# 20241105.net
KiCad netlist of a schematic drawn in Altium Designer
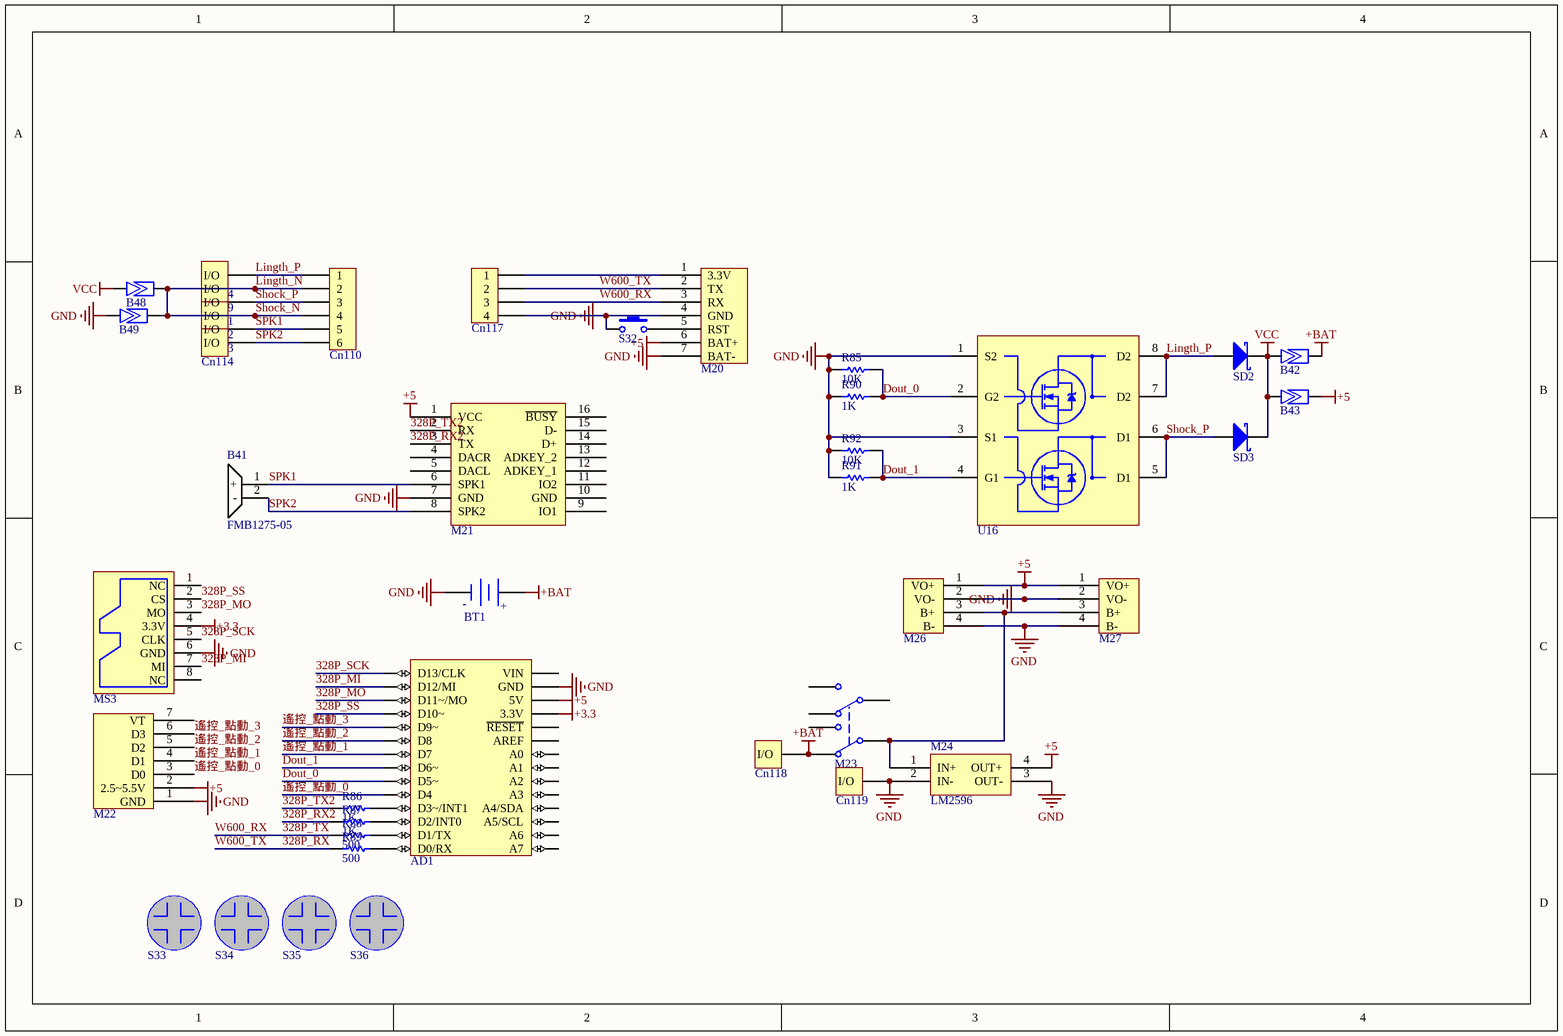
[diagram p0: 松菸_幻影光靈_屍禁_提燈_20241105.SchDoc]

(export (version "E")
  (design (tool "Eeschema 10.0.6"))
  (components
    (comp (ref "AD1")
      (value "Arduino NANO")
      (footprint "Arduino NANO")
      (description "單晶片")
      (libsource (lib "MyLibray") (part "Arduino NANO"))
    )
    (comp (ref "B41")
      (value "FMB1275-05")
      (footprint "Buzzer_12085")
      (description "無源蜂鳴器")
      (libsource (lib "MyLibray") (part "Buzzer"))
    )
    (comp (ref "B42")
      (value "短路")
      (footprint "BYPASS-0805")
      (description "短路焊點(如標註短路則需額外補錫使其短路)")
      (libsource (lib "MyLibray") (part "Bypass"))
    )
    (comp (ref "B43")
      (value "短路")
      (footprint "BYPASS-0805")
      (description "短路焊點(如標註短路則需額外補錫使其短路)")
      (libsource (lib "MyLibray") (part "Bypass"))
    )
    (comp (ref "B48")
      (value "短路")
      (footprint "BYPASS-0805")
      (description "短路焊點(如標註短路則需額外補錫使其短路)")
      (libsource (lib "MyLibray") (part "Bypass"))
    )
    (comp (ref "B49")
      (value "短路")
      (footprint "BYPASS-0805")
      (description "短路焊點(如標註短路則需額外補錫使其短路)")
      (libsource (lib "MyLibray") (part "Bypass"))
    )
    (comp (ref "BT1")
      (value "18650")
      (footprint "Battery_18650")
      (description "電池")
      (libsource (lib "MyLibray") (part "Battery"))
    )
    (comp (ref "Cn104")
      (value "Contact")
      (footprint "Conntact_Stamp hole_0.6\"")
      (description "接線端子、接點、郵票孔(非焊接元件)")
      (libsource (lib "MyLibray") (part "Conntact"))
    )
    (comp (ref "Cn109")
      (value "Contact")
      (footprint "Conntact_Stamp hole_0.6\"")
      (description "接線端子、接點、郵票孔(非焊接元件)")
      (libsource (lib "") (part "Conntact_1"))
    )
    (comp (ref "Cn110")
      (value "KF2510-6")
      (footprint "Connector_KF2510-6A")
      (description "連接器")
      (libsource (lib "MyLibray") (part "Conntact(6P)"))
    )
    (comp (ref "Cn111")
      (value "Contact")
      (footprint "Conntact_Stamp hole_0.6\"")
      (description "接線端子、接點、郵票孔(非焊接元件)")
      (libsource (lib "MyLibray") (part "Conntact"))
    )
    (comp (ref "Cn112")
      (value "Contact")
      (footprint "Conntact_Stamp hole_0.6\"")
      (description "接線端子、接點、郵票孔(非焊接元件)")
      (libsource (lib "MyLibray") (part "Conntact"))
    )
    (comp (ref "Cn113")
      (value "Contact")
      (footprint "Conntact_Stamp hole_0.6\"")
      (description "接線端子、接點、郵票孔(非焊接元件)")
      (libsource (lib "MyLibray") (part "Conntact"))
    )
    (comp (ref "Cn114")
      (value "Contact")
      (footprint "Conntact_Stamp hole_0.6\"")
      (description "接線端子、接點、郵票孔(非焊接元件)")
      (libsource (lib "MyLibray") (part "Conntact"))
    )
    (comp (ref "Cn117")
      (value "KF2510-4")
      (footprint "Connector_KF2510-4A")
      (description "連接器")
      (libsource (lib "MyLibray") (part "Conntact(4P)"))
    )
    (comp (ref "Cn118")
      (value "Contact")
      (footprint "Conntact_Stamp hole_0.6\"")
      (description "接線端子、接點、郵票孔(非焊接元件)")
      (libsource (lib "MyLibray") (part "Conntact"))
    )
    (comp (ref "Cn119")
      (value "Contact")
      (footprint "Conntact_Stamp hole_0.6\"")
      (description "接線端子、接點、郵票孔(非焊接元件)")
      (libsource (lib "MyLibray") (part "Conntact"))
    )
    (comp (ref "M20")
      (value "HH_W600_V2.0")
      (footprint "HH_W600_V2.0")
      (libsource (lib "MyLibray") (part "HH_W600_V2.0"))
    )
    (comp (ref "M21")
      (value "mp3-tf-16p")
      (footprint "BY8001-16P")
      (description "TTL通訊SD卡撥放mp3模組")
      (libsource (lib "MyLibray") (part "Mini MP3 Player"))
    )
    (comp (ref "M22")
      (value "XR390")
      (footprint "XR390 Module")
      (description "遙控器模組")
      (libsource (lib "MyLibray") (part "XR390"))
    )
    (comp (ref "M23")
      (value "MST22D18G2")
      (footprint "Switch_MST22D18G2")
      (description "開關_滑動_2通道")
      (libsource (lib "MyLibray") (part "Switch_Slide_2"))
    )
    (comp (ref "M24")
      (value "LM2596")
      (footprint "LM2596 Module")
      (description "DC to DC 降壓模組")
      (libsource (lib "MyLibray") (part "LM2596_Moduld"))
    )
    (comp (ref "M26")
      (value "4056+LN2220PAR_Module")
      (footprint "4056H+DW01A_Module")
      (description "鋰電池充電升壓模組")
      (libsource (lib "MyLibray") (part "4056+LN2220PAR_Module"))
    )
    (comp (ref "M27")
      (value "4056+LN2220PAR_Module")
      (footprint "4056H+DW01A_Module")
      (description "鋰電池充電升壓模組")
      (libsource (lib "") (part "4056+LN2220PAR_Module_1"))
    )
    (comp (ref "MS3")
      (value "Interface_MicroSD card slot")
      (footprint "Interface_MicroSD card slot")
      (description "Micro SD 卡座")
      (libsource (lib "MyLibray") (part "Interface_MicroSD card slot"))
    )
    (comp (ref "R85")
      (value "10K")
      (footprint "Res-1206")
      (description "電阻")
      (libsource (lib "MyLibray") (part "Res"))
    )
    (comp (ref "R86")
      (value "1K")
      (footprint "Res-1206")
      (description "電阻")
      (libsource (lib "MyLibray") (part "Res"))
    )
    (comp (ref "R87")
      (value "1K")
      (footprint "Res-1206")
      (description "電阻")
      (libsource (lib "MyLibray") (part "Res"))
    )
    (comp (ref "R88")
      (value "500")
      (footprint "Res-1206")
      (description "電阻")
      (libsource (lib "MyLibray") (part "Res"))
    )
    (comp (ref "R89")
      (value "500")
      (footprint "Res-1206")
      (description "電阻")
      (libsource (lib "MyLibray") (part "Res"))
    )
    (comp (ref "R90")
      (value "1K")
      (footprint "Res-1206")
      (description "電阻")
      (libsource (lib "MyLibray") (part "Res"))
    )
    (comp (ref "R91")
      (value "1K")
      (footprint "Res-1206")
      (description "電阻")
      (libsource (lib "MyLibray") (part "Res"))
    )
    (comp (ref "R92")
      (value "10K")
      (footprint "Res-1206")
      (description "電阻")
      (libsource (lib "MyLibray") (part "Res"))
    )
    (comp (ref "S32")
      (value "Switch")
      (footprint "Switch SMD-3.6*6*2.5")
      (description "開關_按鍵")
      (libsource (lib "MyLibray") (part "Switch"))
    )
    (comp (ref "S33")
      (value "M3")
      (footprint "Screw M3")
      (description "螺絲(非焊接元件)")
      (libsource (lib "MyLibray") (part "Screw"))
    )
    (comp (ref "S34")
      (value "M3")
      (footprint "Screw M3")
      (description "螺絲(非焊接元件)")
      (libsource (lib "MyLibray") (part "Screw"))
    )
    (comp (ref "S35")
      (value "M3")
      (footprint "Screw M3")
      (description "螺絲(非焊接元件)")
      (libsource (lib "MyLibray") (part "Screw"))
    )
    (comp (ref "S36")
      (value "M3")
      (footprint "Screw M3")
      (description "螺絲(非焊接元件)")
      (libsource (lib "MyLibray") (part "Screw"))
    )
    (comp (ref "SD2")
      (value "SS56")
      (footprint "Diode_SMA")
      (description "二極體_蕭特基")
      (libsource (lib "MyLibray") (part "Diode_Schottky"))
    )
    (comp (ref "SD3")
      (value "SS56")
      (footprint "Diode_SMA")
      (description "二極體_蕭特基")
      (libsource (lib "MyLibray") (part "Diode_Schottky"))
    )
    (comp (ref "U16")
      (value "AO4800")
      (footprint "SOP-8")
      (description "MOS,雙NMOS")
      (libsource (lib "MyLibray") (part "MOS_Dual N_AO4800"))
    )
  )
  (nets
    (net (code "1") (name "+3.3") (class "Default")
      (node (ref "AD1") (pin "5") (pinfunction "3.3V_5") (pintype "passive"))
      (node (ref "MS3") (pin "4") (pinfunction "3.3V_4") (pintype "power_in"))
    )
    (net (code "2") (name "+5") (class "Default")
      (node (ref "AD1") (pin "3") (pinfunction "5V_3") (pintype "passive"))
      (node (ref "B43") (pin "1") (pinfunction "1_1") (pintype "passive"))
      (node (ref "M20") (pin "6") (pinfunction "BAT+_6") (pintype "passive"))
      (node (ref "M21") (pin "1") (pinfunction "VCC_1") (pintype "passive"))
      (node (ref "M22") (pin "2") (pinfunction "2.5~5.5V_2") (pintype "passive"))
      (node (ref "M24") (pin "4") (pinfunction "OUT+_4") (pintype "passive"))
      (node (ref "M26") (pin "1") (pinfunction "VO+_1") (pintype "passive"))
      (node (ref "M27") (pin "1") (pinfunction "VO+_1") (pintype "passive"))
    )
    (net (code "3") (name "+BAT") (class "Default")
      (node (ref "B42") (pin "1") (pinfunction "1_1") (pintype "passive"))
      (node (ref "BT1") (pin "1") (pinfunction "+_1") (pintype "power_in"))
      (node (ref "Cn118") (pin "1") (pinfunction "I/O_1") (pintype "passive"))
      (node (ref "M23") (pin "2") (pinfunction "2_2") (pintype "passive"))
    )
    (net (code "4") (name "/328P_MI") (class "Default")
      (node (ref "AD1") (pin "19") (pinfunction "D12/MI_19") (pintype "bidirectional"))
      (node (ref "MS3") (pin "7") (pinfunction "MI_7") (pintype "passive"))
    )
    (net (code "5") (name "/328P_MO") (class "Default")
      (node (ref "AD1") (pin "18") (pinfunction "D11~/MO_18") (pintype "bidirectional"))
      (node (ref "MS3") (pin "3") (pinfunction "MO_3") (pintype "passive"))
    )
    (net (code "6") (name "/328P_RX") (class "Default")
      (node (ref "Cn117") (pin "2") (pinfunction "2_2") (pintype "passive"))
      (node (ref "M20") (pin "2") (pinfunction "TX_2") (pintype "passive"))
      (node (ref "R89") (pin "1") (pinfunction "1_1") (pintype "passive"))
    )
    (net (code "7") (name "/328P_RX2") (class "Default")
      (node (ref "M21") (pin "3") (pinfunction "TX_3") (pintype "passive"))
      (node (ref "R87") (pin "1") (pinfunction "1_1") (pintype "passive"))
    )
    (net (code "8") (name "/328P_SCK") (class "Default")
      (node (ref "AD1") (pin "20") (pinfunction "D13/CLK_20") (pintype "bidirectional"))
      (node (ref "MS3") (pin "5") (pinfunction "CLK_5") (pintype "passive"))
    )
    (net (code "9") (name "/328P_SS") (class "Default")
      (node (ref "AD1") (pin "17") (pinfunction "D10~_17") (pintype "bidirectional"))
      (node (ref "MS3") (pin "2") (pinfunction "CS_2") (pintype "passive"))
    )
    (net (code "10") (name "/328P_TX") (class "Default")
      (node (ref "Cn117") (pin "3") (pinfunction "3_3") (pintype "passive"))
      (node (ref "M20") (pin "3") (pinfunction "RX_3") (pintype "passive"))
      (node (ref "R88") (pin "1") (pinfunction "1_1") (pintype "passive"))
    )
    (net (code "11") (name "/328P_TX2") (class "Default")
      (node (ref "M21") (pin "2") (pinfunction "RX_2") (pintype "passive"))
      (node (ref "R86") (pin "1") (pinfunction "1_1") (pintype "passive"))
    )
    (net (code "12") (name "/Dout_0") (class "Default")
      (node (ref "AD1") (pin "12") (pinfunction "D5~_12") (pintype "bidirectional"))
      (node (ref "R85") (pin "2") (pinfunction "2_2") (pintype "passive"))
      (node (ref "R90") (pin "2") (pinfunction "2_2") (pintype "passive"))
      (node (ref "U16") (pin "2") (pinfunction "G2_2") (pintype "passive"))
    )
    (net (code "13") (name "/Dout_1") (class "Default")
      (node (ref "AD1") (pin "13") (pinfunction "D6~_13") (pintype "bidirectional"))
      (node (ref "R91") (pin "2") (pinfunction "2_2") (pintype "passive"))
      (node (ref "R92") (pin "2") (pinfunction "2_2") (pintype "passive"))
      (node (ref "U16") (pin "4") (pinfunction "G1_4") (pintype "passive"))
    )
    (net (code "14") (name "/Lingth_N") (class "Default")
      (node (ref "B48") (pin "1") (pinfunction "1_1") (pintype "passive"))
      (node (ref "B49") (pin "1") (pinfunction "1_1") (pintype "passive"))
      (node (ref "Cn109") (pin "1") (pinfunction "I/O_1") (pintype "passive"))
      (node (ref "Cn110") (pin "2") (pinfunction "2_2") (pintype "passive"))
      (node (ref "Cn110") (pin "4") (pinfunction "4_4") (pintype "passive"))
      (node (ref "Cn112") (pin "1") (pinfunction "I/O_1") (pintype "passive"))
    )
    (net (code "15") (name "/Lingth_P") (class "Default")
      (node (ref "Cn104") (pin "1") (pinfunction "I/O_1") (pintype "passive"))
      (node (ref "Cn110") (pin "1") (pinfunction "1_1") (pintype "passive"))
      (node (ref "SD2") (pin "2") (pinfunction "A_2") (pintype "passive"))
      (node (ref "U16") (pin "7") (pinfunction "D2_7") (pintype "passive"))
      (node (ref "U16") (pin "8") (pinfunction "D2_8") (pintype "passive"))
    )
    (net (code "16") (name "/SPK1") (class "Default")
      (node (ref "B41") (pin "1") (pinfunction "+_1") (pintype "passive"))
      (node (ref "Cn110") (pin "5") (pinfunction "5_5") (pintype "passive"))
      (node (ref "Cn113") (pin "1") (pinfunction "I/O_1") (pintype "passive"))
      (node (ref "M21") (pin "6") (pinfunction "SPK1_6") (pintype "passive"))
    )
    (net (code "17") (name "/SPK2") (class "Default")
      (node (ref "B41") (pin "2") (pinfunction "-_2") (pintype "passive"))
      (node (ref "Cn110") (pin "6") (pinfunction "6_6") (pintype "passive"))
      (node (ref "Cn114") (pin "1") (pinfunction "I/O_1") (pintype "passive"))
      (node (ref "M21") (pin "8") (pinfunction "SPK2_8") (pintype "passive"))
    )
    (net (code "18") (name "/Shock_P") (class "Default")
      (node (ref "Cn110") (pin "3") (pinfunction "3_3") (pintype "passive"))
      (node (ref "Cn111") (pin "1") (pinfunction "I/O_1") (pintype "passive"))
      (node (ref "SD3") (pin "2") (pinfunction "A_2") (pintype "passive"))
      (node (ref "U16") (pin "5") (pinfunction "D1_5") (pintype "passive"))
      (node (ref "U16") (pin "6") (pinfunction "D1_6") (pintype "passive"))
    )
    (net (code "19") (name "/遙控_點動_0") (class "Default")
      (node (ref "AD1") (pin "11") (pinfunction "D4_11") (pintype "bidirectional"))
      (node (ref "M22") (pin "3") (pinfunction "D0_3") (pintype "passive"))
    )
    (net (code "20") (name "/遙控_點動_1") (class "Default")
      (node (ref "AD1") (pin "14") (pinfunction "D7_14") (pintype "bidirectional"))
      (node (ref "M22") (pin "4") (pinfunction "D1_4") (pintype "passive"))
    )
    (net (code "21") (name "/遙控_點動_2") (class "Default")
      (node (ref "AD1") (pin "15") (pinfunction "D8_15") (pintype "bidirectional"))
      (node (ref "M22") (pin "5") (pinfunction "D2_5") (pintype "passive"))
    )
    (net (code "22") (name "/遙控_點動_3") (class "Default")
      (node (ref "AD1") (pin "16") (pinfunction "D9~_16") (pintype "bidirectional"))
      (node (ref "M22") (pin "6") (pinfunction "D3_6") (pintype "passive"))
    )
    (net (code "23") (name "GND") (class "Default")
      (node (ref "AD1") (pin "2") (pinfunction "GND_2") (pintype "passive"))
      (node (ref "B49") (pin "2") (pinfunction "2_2") (pintype "passive"))
      (node (ref "BT1") (pin "2") (pinfunction "-_2") (pintype "power_in"))
      (node (ref "Cn117") (pin "4") (pinfunction "4_4") (pintype "passive"))
      (node (ref "Cn119") (pin "1") (pinfunction "I/O_1") (pintype "passive"))
      (node (ref "M20") (pin "4") (pinfunction "GND_4") (pintype "passive"))
      (node (ref "M20") (pin "7") (pinfunction "BAT-_7") (pintype "passive"))
      (node (ref "M21") (pin "7") (pinfunction "GND_7") (pintype "passive"))
      (node (ref "M22") (pin "1") (pinfunction "GND_1") (pintype "passive"))
      (node (ref "M24") (pin "2") (pinfunction "IN-_2") (pintype "passive"))
      (node (ref "M24") (pin "3") (pinfunction "OUT-_3") (pintype "passive"))
      (node (ref "M26") (pin "2") (pinfunction "VO-_2") (pintype "passive"))
      (node (ref "M26") (pin "4") (pinfunction "B-_4") (pintype "passive"))
      (node (ref "M27") (pin "2") (pinfunction "VO-_2") (pintype "passive"))
      (node (ref "M27") (pin "4") (pinfunction "B-_4") (pintype "passive"))
      (node (ref "MS3") (pin "6") (pinfunction "GND_6") (pintype "power_in"))
      (node (ref "R85") (pin "1") (pinfunction "1_1") (pintype "passive"))
      (node (ref "R90") (pin "1") (pinfunction "1_1") (pintype "passive"))
      (node (ref "R91") (pin "1") (pinfunction "1_1") (pintype "passive"))
      (node (ref "R92") (pin "1") (pinfunction "1_1") (pintype "passive"))
      (node (ref "S32") (pin "1") (pinfunction "1_1") (pintype "passive"))
      (node (ref "U16") (pin "1") (pinfunction "S2_1") (pintype "passive"))
      (node (ref "U16") (pin "3") (pinfunction "S1_3") (pintype "passive"))
    )
    (net (code "24") (name "Net-(AD1-D0{slash}RX)") (class "Default")
      (node (ref "AD1") (pin "7") (pinfunction "D0/RX_7") (pintype "bidirectional"))
      (node (ref "R89") (pin "2") (pinfunction "2_2") (pintype "passive"))
    )
    (net (code "25") (name "Net-(AD1-D1{slash}TX)") (class "Default")
      (node (ref "AD1") (pin "8") (pinfunction "D1/TX_8") (pintype "bidirectional"))
      (node (ref "R88") (pin "2") (pinfunction "2_2") (pintype "passive"))
    )
    (net (code "26") (name "Net-(AD1-D2{slash}INT0)") (class "Default")
      (node (ref "AD1") (pin "9") (pinfunction "D2/INT0_9") (pintype "bidirectional"))
      (node (ref "R87") (pin "2") (pinfunction "2_2") (pintype "passive"))
    )
    (net (code "27") (name "Net-(AD1-D3~{slash}INT1)") (class "Default")
      (node (ref "AD1") (pin "10") (pinfunction "D3~/INT1_10") (pintype "bidirectional"))
      (node (ref "R86") (pin "2") (pinfunction "2_2") (pintype "passive"))
    )
    (net (code "28") (name "Net-(M20-3.3V)") (class "Default")
      (node (ref "Cn117") (pin "1") (pinfunction "1_1") (pintype "passive"))
      (node (ref "M20") (pin "1") (pinfunction "3.3V_1") (pintype "passive"))
    )
    (net (code "29") (name "Net-(M20-RST)") (class "Default")
      (node (ref "M20") (pin "5") (pinfunction "RST_5") (pintype "passive"))
      (node (ref "S32") (pin "2") (pinfunction "2_2") (pintype "passive"))
    )
    (net (code "30") (name "Net-(M24-IN+)") (class "Default")
      (node (ref "M23") (pin "1") (pinfunction "1_1") (pintype "passive"))
      (node (ref "M24") (pin "1") (pinfunction "IN+_1") (pintype "passive"))
      (node (ref "M26") (pin "3") (pinfunction "B+_3") (pintype "passive"))
      (node (ref "M27") (pin "3") (pinfunction "B+_3") (pintype "passive"))
    )
    (net (code "31") (name "VCC") (class "Default")
      (node (ref "B42") (pin "2") (pinfunction "2_2") (pintype "passive"))
      (node (ref "B43") (pin "2") (pinfunction "2_2") (pintype "passive"))
      (node (ref "B48") (pin "2") (pinfunction "2_2") (pintype "passive"))
      (node (ref "SD2") (pin "1") (pinfunction "K_1") (pintype "passive"))
      (node (ref "SD3") (pin "1") (pinfunction "K_1") (pintype "passive"))
    )
    (net (code "32") (name "unconnected-(AD1-A0-Pad21)") (class "Default")
      (node (ref "AD1") (pin "21") (pinfunction "A0_21") (pintype "bidirectional"))
    )
    (net (code "33") (name "unconnected-(AD1-A1-Pad22)") (class "Default")
      (node (ref "AD1") (pin "22") (pinfunction "A1_22") (pintype "bidirectional"))
    )
    (net (code "34") (name "unconnected-(AD1-A2-Pad23)") (class "Default")
      (node (ref "AD1") (pin "23") (pinfunction "A2_23") (pintype "bidirectional"))
    )
    (net (code "35") (name "unconnected-(AD1-A3-Pad24)") (class "Default")
      (node (ref "AD1") (pin "24") (pinfunction "A3_24") (pintype "bidirectional"))
    )
    (net (code "36") (name "unconnected-(AD1-A4{slash}SDA-Pad25)") (class "Default")
      (node (ref "AD1") (pin "25") (pinfunction "A4/SDA_25") (pintype "bidirectional"))
    )
    (net (code "37") (name "unconnected-(AD1-A5{slash}SCL-Pad26)") (class "Default")
      (node (ref "AD1") (pin "26") (pinfunction "A5/SCL_26") (pintype "bidirectional"))
    )
    (net (code "38") (name "unconnected-(AD1-A6-Pad27)") (class "Default")
      (node (ref "AD1") (pin "27") (pinfunction "A6_27") (pintype "bidirectional"))
    )
    (net (code "39") (name "unconnected-(AD1-A7-Pad28)") (class "Default")
      (node (ref "AD1") (pin "28") (pinfunction "A7_28") (pintype "bidirectional"))
    )
    (net (code "40") (name "unconnected-(AD1-AREF-Pad6)") (class "Default")
      (node (ref "AD1") (pin "6") (pinfunction "AREF_6") (pintype "passive"))
    )
    (net (code "41") (name "unconnected-(AD1-VIN-Pad1)") (class "Default")
      (node (ref "AD1") (pin "1") (pinfunction "VIN_1") (pintype "passive"))
    )
    (net (code "42") (name "unconnected-(AD1-~{RESET}-Pad4)") (class "Default")
      (node (ref "AD1") (pin "4") (pinfunction "~{RESET}_4") (pintype "passive"))
    )
    (net (code "43") (name "unconnected-(M21-ADKEY_1-Pad12)") (class "Default")
      (node (ref "M21") (pin "12") (pinfunction "ADKEY_1_12") (pintype "passive"))
    )
    (net (code "44") (name "unconnected-(M21-ADKEY_2-Pad13)") (class "Default")
      (node (ref "M21") (pin "13") (pinfunction "ADKEY_2_13") (pintype "passive"))
    )
    (net (code "45") (name "unconnected-(M21-D+-Pad14)") (class "Default")
      (node (ref "M21") (pin "14") (pinfunction "D+_14") (pintype "passive"))
    )
    (net (code "46") (name "unconnected-(M21-D--Pad15)") (class "Default")
      (node (ref "M21") (pin "15") (pinfunction "D-_15") (pintype "passive"))
    )
    (net (code "47") (name "unconnected-(M21-DACL-Pad5)") (class "Default")
      (node (ref "M21") (pin "5") (pinfunction "DACL_5") (pintype "passive"))
    )
    (net (code "48") (name "unconnected-(M21-DACR-Pad4)") (class "Default")
      (node (ref "M21") (pin "4") (pinfunction "DACR_4") (pintype "passive"))
    )
    (net (code "49") (name "unconnected-(M21-GND-Pad10)") (class "Default")
      (node (ref "M21") (pin "10") (pinfunction "GND_10") (pintype "passive"))
    )
    (net (code "50") (name "unconnected-(M21-IO1-Pad9)") (class "Default")
      (node (ref "M21") (pin "9") (pinfunction "IO1_9") (pintype "passive"))
    )
    (net (code "51") (name "unconnected-(M21-IO2-Pad11)") (class "Default")
      (node (ref "M21") (pin "11") (pinfunction "IO2_11") (pintype "passive"))
    )
    (net (code "52") (name "unconnected-(M21-~{BUSY}-Pad16)") (class "Default")
      (node (ref "M21") (pin "16") (pinfunction "~{BUSY}_16") (pintype "passive"))
    )
    (net (code "53") (name "unconnected-(M22-VT-Pad7)") (class "Default")
      (node (ref "M22") (pin "7") (pinfunction "VT_7") (pintype "passive"))
    )
    (net (code "54") (name "unconnected-(M23-Pad3)") (class "Default")
      (node (ref "M23") (pin "3") (pinfunction "3_3") (pintype "passive"))
    )
    (net (code "55") (name "unconnected-(M23-Pad4)") (class "Default")
      (node (ref "M23") (pin "4") (pinfunction "4_4") (pintype "passive"))
    )
    (net (code "56") (name "unconnected-(M23-Pad5)") (class "Default")
      (node (ref "M23") (pin "5") (pinfunction "5_5") (pintype "passive"))
    )
    (net (code "57") (name "unconnected-(M23-Pad6)") (class "Default")
      (node (ref "M23") (pin "6") (pinfunction "6_6") (pintype "passive"))
    )
    (net (code "58") (name "unconnected-(MS3-NC-Pad1)") (class "Default")
      (node (ref "MS3") (pin "1") (pinfunction "NC_1") (pintype "passive"))
    )
    (net (code "59") (name "unconnected-(MS3-NC-Pad8)") (class "Default")
      (node (ref "MS3") (pin "8") (pinfunction "NC_8") (pintype "passive"))
    )
  )
)
